# Assignment1-5VAC-DCCRegulator.net
KiCad netlist of a schematic drawn in EAGLE
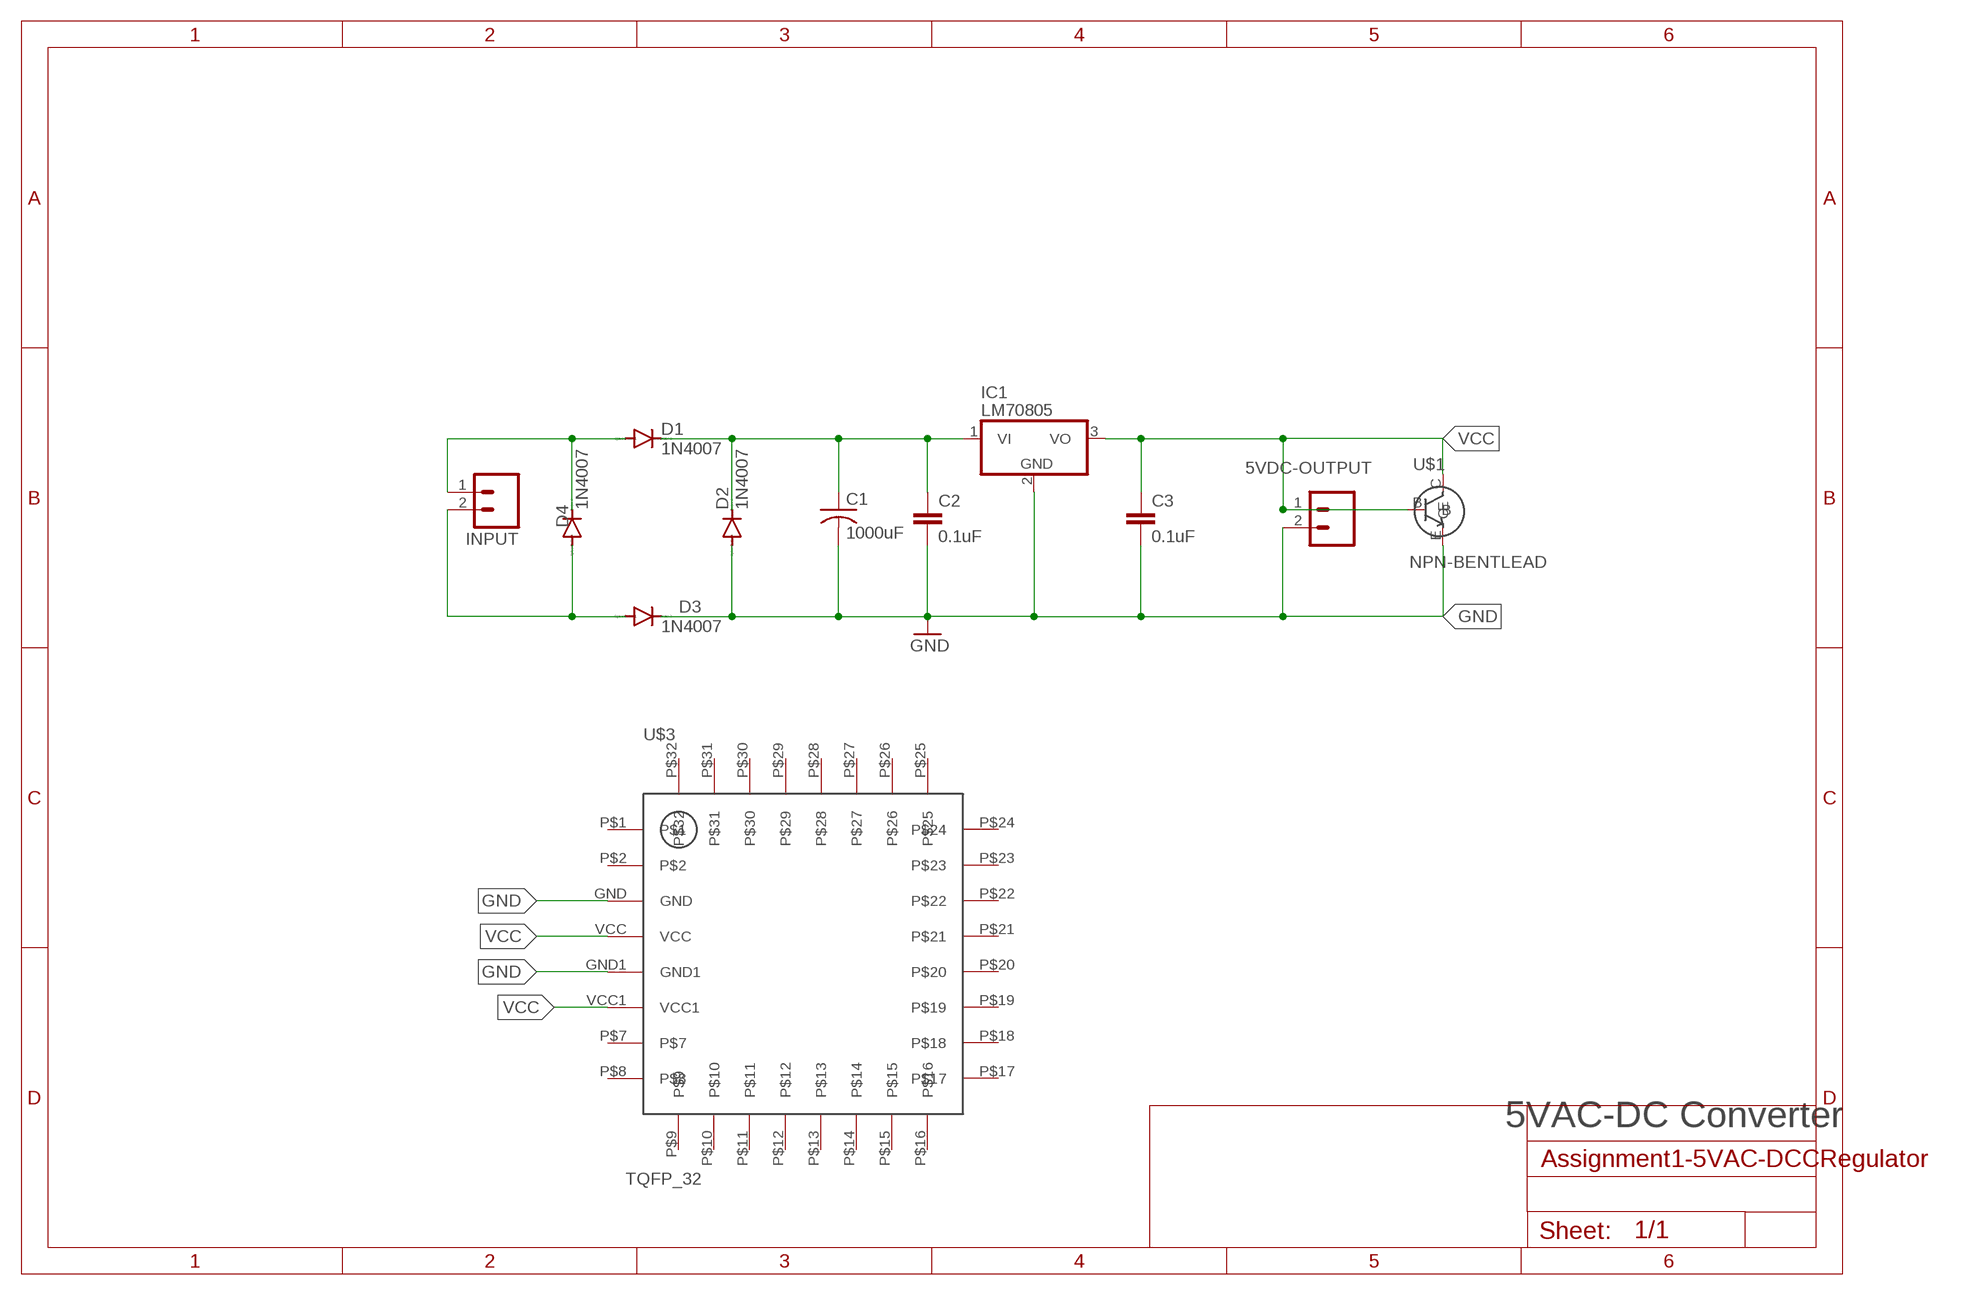
[diagram p0: schematic, sheet 1]

(export (version "E")
  (design (tool "Eeschema 10.0.6"))
  (components
    (comp (ref "5VDC-OUTPUT")
      (value "M02")
      (footprint "eagle-import:02P")
      (libsource (lib "eagle-import") (part "M02"))
    )
    (comp (ref "C1")
      (value "1000uF")
      (footprint "eagle-import:C025-024X044")
      (libsource (lib "eagle-import") (part "C-US025-024X044"))
    )
    (comp (ref "C2")
      (value "0.1uF")
      (footprint "eagle-import:C025-025X050")
      (libsource (lib "eagle-import") (part "C-EU025-025X050"))
    )
    (comp (ref "C3")
      (value "0.1uF")
      (footprint "eagle-import:C025-025X050")
      (libsource (lib "eagle-import") (part "C-EU025-025X050"))
    )
    (comp (ref "D1")
      (value "1N4007")
      (footprint "eagle-import:DO41-10")
      (libsource (lib "eagle-import") (part "1N4004"))
    )
    (comp (ref "D2")
      (value "1N4007")
      (footprint "eagle-import:DO41-10")
      (libsource (lib "eagle-import") (part "1N4004"))
    )
    (comp (ref "D3")
      (value "1N4007")
      (footprint "eagle-import:DO41-10")
      (libsource (lib "eagle-import") (part "1N4004"))
    )
    (comp (ref "D4")
      (value "1N4007")
      (footprint "eagle-import:DO41-10")
      (libsource (lib "eagle-import") (part "1N4004"))
    )
    (comp (ref "IC1")
      (value "LM70805")
      (footprint "eagle-import:TO220V")
      (libsource (lib "eagle-import") (part "78TV6"))
    )
    (comp (ref "INPUT")
      (value "M02")
      (footprint "eagle-import:02P")
      (libsource (lib "eagle-import") (part "M02"))
    )
    (comp (ref "U$1")
      (value "NPN-BENTLEAD")
      (footprint "eagle-import:BENT-LEAD")
      (libsource (lib "eagle-import") (part "NPN-BENTLEAD"))
    )
    (comp (ref "U$3")
      (value "TQFP_32")
      (footprint "eagle-import:TQFP_32")
      (libsource (lib "eagle-import") (part "TQFP_32"))
    )
  )
  (nets
    (net (code "1") (name "GND") (class "Default")
      (node (ref "5VDC-OUTPUT") (pin "2") (pinfunction "2_2") (pintype "passive"))
      (node (ref "C1") (pin "2") (pinfunction "2_2") (pintype "passive"))
      (node (ref "C2") (pin "2") (pinfunction "2_2") (pintype "passive"))
      (node (ref "C3") (pin "2") (pinfunction "2_2") (pintype "passive"))
      (node (ref "D2") (pin "A") (pinfunction "A_A") (pintype "passive"))
      (node (ref "D3") (pin "C") (pinfunction "C_C") (pintype "passive"))
      (node (ref "IC1") (pin "2") (pinfunction "GND_2") (pintype "passive"))
      (node (ref "U$1") (pin "E") (pinfunction "E_E") (pintype "bidirectional"))
      (node (ref "U$3") (pin "GND") (pinfunction "GND_GND") (pintype "bidirectional"))
      (node (ref "U$3") (pin "GND1") (pinfunction "GND1_GND1") (pintype "bidirectional"))
    )
    (net (code "2") (name "Net-(D1-PadA)") (class "Default")
      (node (ref "D1") (pin "A") (pinfunction "A_A") (pintype "passive"))
      (node (ref "D4") (pin "C") (pinfunction "C_C") (pintype "passive"))
      (node (ref "INPUT") (pin "1") (pinfunction "1_1") (pintype "passive"))
    )
    (net (code "3") (name "Net-(D3-PadA)") (class "Default")
      (node (ref "D3") (pin "A") (pinfunction "A_A") (pintype "passive"))
      (node (ref "D4") (pin "A") (pinfunction "A_A") (pintype "passive"))
      (node (ref "INPUT") (pin "2") (pinfunction "2_2") (pintype "passive"))
    )
    (net (code "4") (name "Net-(IC1-VI)") (class "Default")
      (node (ref "C1") (pin "1") (pinfunction "1_1") (pintype "passive"))
      (node (ref "C2") (pin "1") (pinfunction "1_1") (pintype "passive"))
      (node (ref "D1") (pin "C") (pinfunction "C_C") (pintype "passive"))
      (node (ref "D2") (pin "C") (pinfunction "C_C") (pintype "passive"))
      (node (ref "IC1") (pin "1") (pinfunction "VI_1") (pintype "input"))
    )
    (net (code "5") (name "VCC") (class "Default")
      (node (ref "5VDC-OUTPUT") (pin "1") (pinfunction "1_1") (pintype "passive"))
      (node (ref "C3") (pin "1") (pinfunction "1_1") (pintype "passive"))
      (node (ref "IC1") (pin "3") (pinfunction "VO_3") (pintype "passive"))
      (node (ref "U$1") (pin "B") (pinfunction "B_B") (pintype "bidirectional"))
      (node (ref "U$1") (pin "C") (pinfunction "C_C") (pintype "bidirectional"))
      (node (ref "U$3") (pin "VCC") (pinfunction "VCC_VCC") (pintype "bidirectional"))
      (node (ref "U$3") (pin "VCC1") (pinfunction "VCC1_VCC1") (pintype "bidirectional"))
    )
    (net (code "6") (name "unconnected-(U$3-PadP$1)") (class "Default")
      (node (ref "U$3") (pin "P$1") (pinfunction "P$1_P$1") (pintype "bidirectional"))
    )
    (net (code "7") (name "unconnected-(U$3-PadP$2)") (class "Default")
      (node (ref "U$3") (pin "P$2") (pinfunction "P$2_P$2") (pintype "bidirectional"))
    )
    (net (code "8") (name "unconnected-(U$3-PadP$7)") (class "Default")
      (node (ref "U$3") (pin "P$7") (pinfunction "P$7_P$7") (pintype "bidirectional"))
    )
    (net (code "9") (name "unconnected-(U$3-PadP$8)") (class "Default")
      (node (ref "U$3") (pin "P$8") (pinfunction "P$8_P$8") (pintype "bidirectional"))
    )
    (net (code "10") (name "unconnected-(U$3-PadP$9)") (class "Default")
      (node (ref "U$3") (pin "P$9") (pinfunction "P$9_P$9") (pintype "bidirectional"))
    )
    (net (code "11") (name "unconnected-(U$3-PadP$10)") (class "Default")
      (node (ref "U$3") (pin "P$10") (pinfunction "P$10_P$10") (pintype "bidirectional"))
    )
    (net (code "12") (name "unconnected-(U$3-PadP$11)") (class "Default")
      (node (ref "U$3") (pin "P$11") (pinfunction "P$11_P$11") (pintype "bidirectional"))
    )
    (net (code "13") (name "unconnected-(U$3-PadP$12)") (class "Default")
      (node (ref "U$3") (pin "P$12") (pinfunction "P$12_P$12") (pintype "bidirectional"))
    )
    (net (code "14") (name "unconnected-(U$3-PadP$13)") (class "Default")
      (node (ref "U$3") (pin "P$13") (pinfunction "P$13_P$13") (pintype "bidirectional"))
    )
    (net (code "15") (name "unconnected-(U$3-PadP$14)") (class "Default")
      (node (ref "U$3") (pin "P$14") (pinfunction "P$14_P$14") (pintype "bidirectional"))
    )
    (net (code "16") (name "unconnected-(U$3-PadP$15)") (class "Default")
      (node (ref "U$3") (pin "P$15") (pinfunction "P$15_P$15") (pintype "bidirectional"))
    )
    (net (code "17") (name "unconnected-(U$3-PadP$16)") (class "Default")
      (node (ref "U$3") (pin "P$16") (pinfunction "P$16_P$16") (pintype "bidirectional"))
    )
    (net (code "18") (name "unconnected-(U$3-PadP$17)") (class "Default")
      (node (ref "U$3") (pin "P$17") (pinfunction "P$17_P$17") (pintype "bidirectional"))
    )
    (net (code "19") (name "unconnected-(U$3-PadP$18)") (class "Default")
      (node (ref "U$3") (pin "P$18") (pinfunction "P$18_P$18") (pintype "bidirectional"))
    )
    (net (code "20") (name "unconnected-(U$3-PadP$19)") (class "Default")
      (node (ref "U$3") (pin "P$19") (pinfunction "P$19_P$19") (pintype "bidirectional"))
    )
    (net (code "21") (name "unconnected-(U$3-PadP$20)") (class "Default")
      (node (ref "U$3") (pin "P$20") (pinfunction "P$20_P$20") (pintype "bidirectional"))
    )
    (net (code "22") (name "unconnected-(U$3-PadP$21)") (class "Default")
      (node (ref "U$3") (pin "P$21") (pinfunction "P$21_P$21") (pintype "bidirectional"))
    )
    (net (code "23") (name "unconnected-(U$3-PadP$22)") (class "Default")
      (node (ref "U$3") (pin "P$22") (pinfunction "P$22_P$22") (pintype "bidirectional"))
    )
    (net (code "24") (name "unconnected-(U$3-PadP$23)") (class "Default")
      (node (ref "U$3") (pin "P$23") (pinfunction "P$23_P$23") (pintype "bidirectional"))
    )
    (net (code "25") (name "unconnected-(U$3-PadP$24)") (class "Default")
      (node (ref "U$3") (pin "P$24") (pinfunction "P$24_P$24") (pintype "bidirectional"))
    )
    (net (code "26") (name "unconnected-(U$3-PadP$25)") (class "Default")
      (node (ref "U$3") (pin "P$25") (pinfunction "P$25_P$25") (pintype "bidirectional"))
    )
    (net (code "27") (name "unconnected-(U$3-PadP$26)") (class "Default")
      (node (ref "U$3") (pin "P$26") (pinfunction "P$26_P$26") (pintype "bidirectional"))
    )
    (net (code "28") (name "unconnected-(U$3-PadP$27)") (class "Default")
      (node (ref "U$3") (pin "P$27") (pinfunction "P$27_P$27") (pintype "bidirectional"))
    )
    (net (code "29") (name "unconnected-(U$3-PadP$28)") (class "Default")
      (node (ref "U$3") (pin "P$28") (pinfunction "P$28_P$28") (pintype "bidirectional"))
    )
    (net (code "30") (name "unconnected-(U$3-PadP$29)") (class "Default")
      (node (ref "U$3") (pin "P$29") (pinfunction "P$29_P$29") (pintype "bidirectional"))
    )
    (net (code "31") (name "unconnected-(U$3-PadP$30)") (class "Default")
      (node (ref "U$3") (pin "P$30") (pinfunction "P$30_P$30") (pintype "bidirectional"))
    )
    (net (code "32") (name "unconnected-(U$3-PadP$31)") (class "Default")
      (node (ref "U$3") (pin "P$31") (pinfunction "P$31_P$31") (pintype "bidirectional"))
    )
    (net (code "33") (name "unconnected-(U$3-PadP$32)") (class "Default")
      (node (ref "U$3") (pin "P$32") (pinfunction "P$32_P$32") (pintype "bidirectional"))
    )
  )
)
